# ShiftRegister.net
KiCad netlist of a schematic drawn in Altium Designer
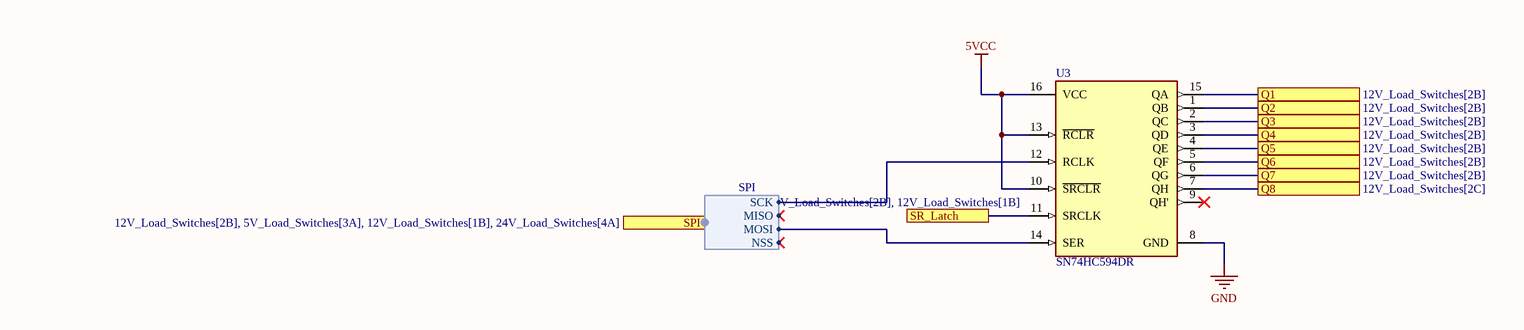
[diagram p0: ShiftRegister.SchDoc]

(export (version "E")
  (design (tool "Eeschema 10.0.6"))
  (components
    (comp (ref "U3")
      (value "SN74HC594DR")
      (footprint "FP-D0016A-IPC_A")
      (description "IC SHIFT REGISTER 8BIT 16-SOIC")
      (libsource (lib "Altium Content Vault") (part "6ffdf0eb1487316571b39b71ede2db7"))
    )
  )
  (nets
    (net (code "2") (name "/MOSI") (class "Default")
      (node (ref "U3") (pin "14") (pinfunction "SER_14") (pintype "input"))
    )
    (net (code "3") (name "/Q1") (class "Default")
      (node (ref "U3") (pin "15") (pinfunction "QA_15") (pintype "output"))
    )
    (net (code "4") (name "/Q2") (class "Default")
      (node (ref "U3") (pin "1") (pinfunction "QB_1") (pintype "output"))
    )
    (net (code "5") (name "/Q3") (class "Default")
      (node (ref "U3") (pin "2") (pinfunction "QC_2") (pintype "output"))
    )
    (net (code "6") (name "/Q4") (class "Default")
      (node (ref "U3") (pin "3") (pinfunction "QD_3") (pintype "output"))
    )
    (net (code "7") (name "/Q5") (class "Default")
      (node (ref "U3") (pin "4") (pinfunction "QE_4") (pintype "output"))
    )
    (net (code "8") (name "/Q6") (class "Default")
      (node (ref "U3") (pin "5") (pinfunction "QF_5") (pintype "output"))
    )
    (net (code "9") (name "/Q7") (class "Default")
      (node (ref "U3") (pin "6") (pinfunction "QG_6") (pintype "output"))
    )
    (net (code "10") (name "/Q8") (class "Default")
      (node (ref "U3") (pin "7") (pinfunction "QH_7") (pintype "output"))
    )
    (net (code "11") (name "/SCK") (class "Default")
      (node (ref "U3") (pin "12") (pinfunction "RCLK_12") (pintype "input"))
    )
    (net (code "12") (name "/SR_Latch") (class "Default")
      (node (ref "U3") (pin "11") (pinfunction "SRCLK_11") (pintype "input"))
    )
    (net (code "14") (name "5VCC") (class "Default")
      (node (ref "U3") (pin "10") (pinfunction "~{SRCLR}_10") (pintype "input"))
      (node (ref "U3") (pin "13") (pinfunction "~{RCLR}_13") (pintype "input"))
      (node (ref "U3") (pin "16") (pinfunction "VCC_16") (pintype "power_in"))
    )
    (net (code "15") (name "GND") (class "Default")
      (node (ref "U3") (pin "8") (pinfunction "GND_8") (pintype "power_in"))
    )
    (net (code "16") (name "unconnected-(U3-QH'-Pad9)") (class "Default")
      (node (ref "U3") (pin "9") (pinfunction "QH'_9") (pintype "output+no_connect"))
    )
  )
)
